# Wilssen_core_v0_206a.net
KiCad netlist of a schematic drawn in EAGLE
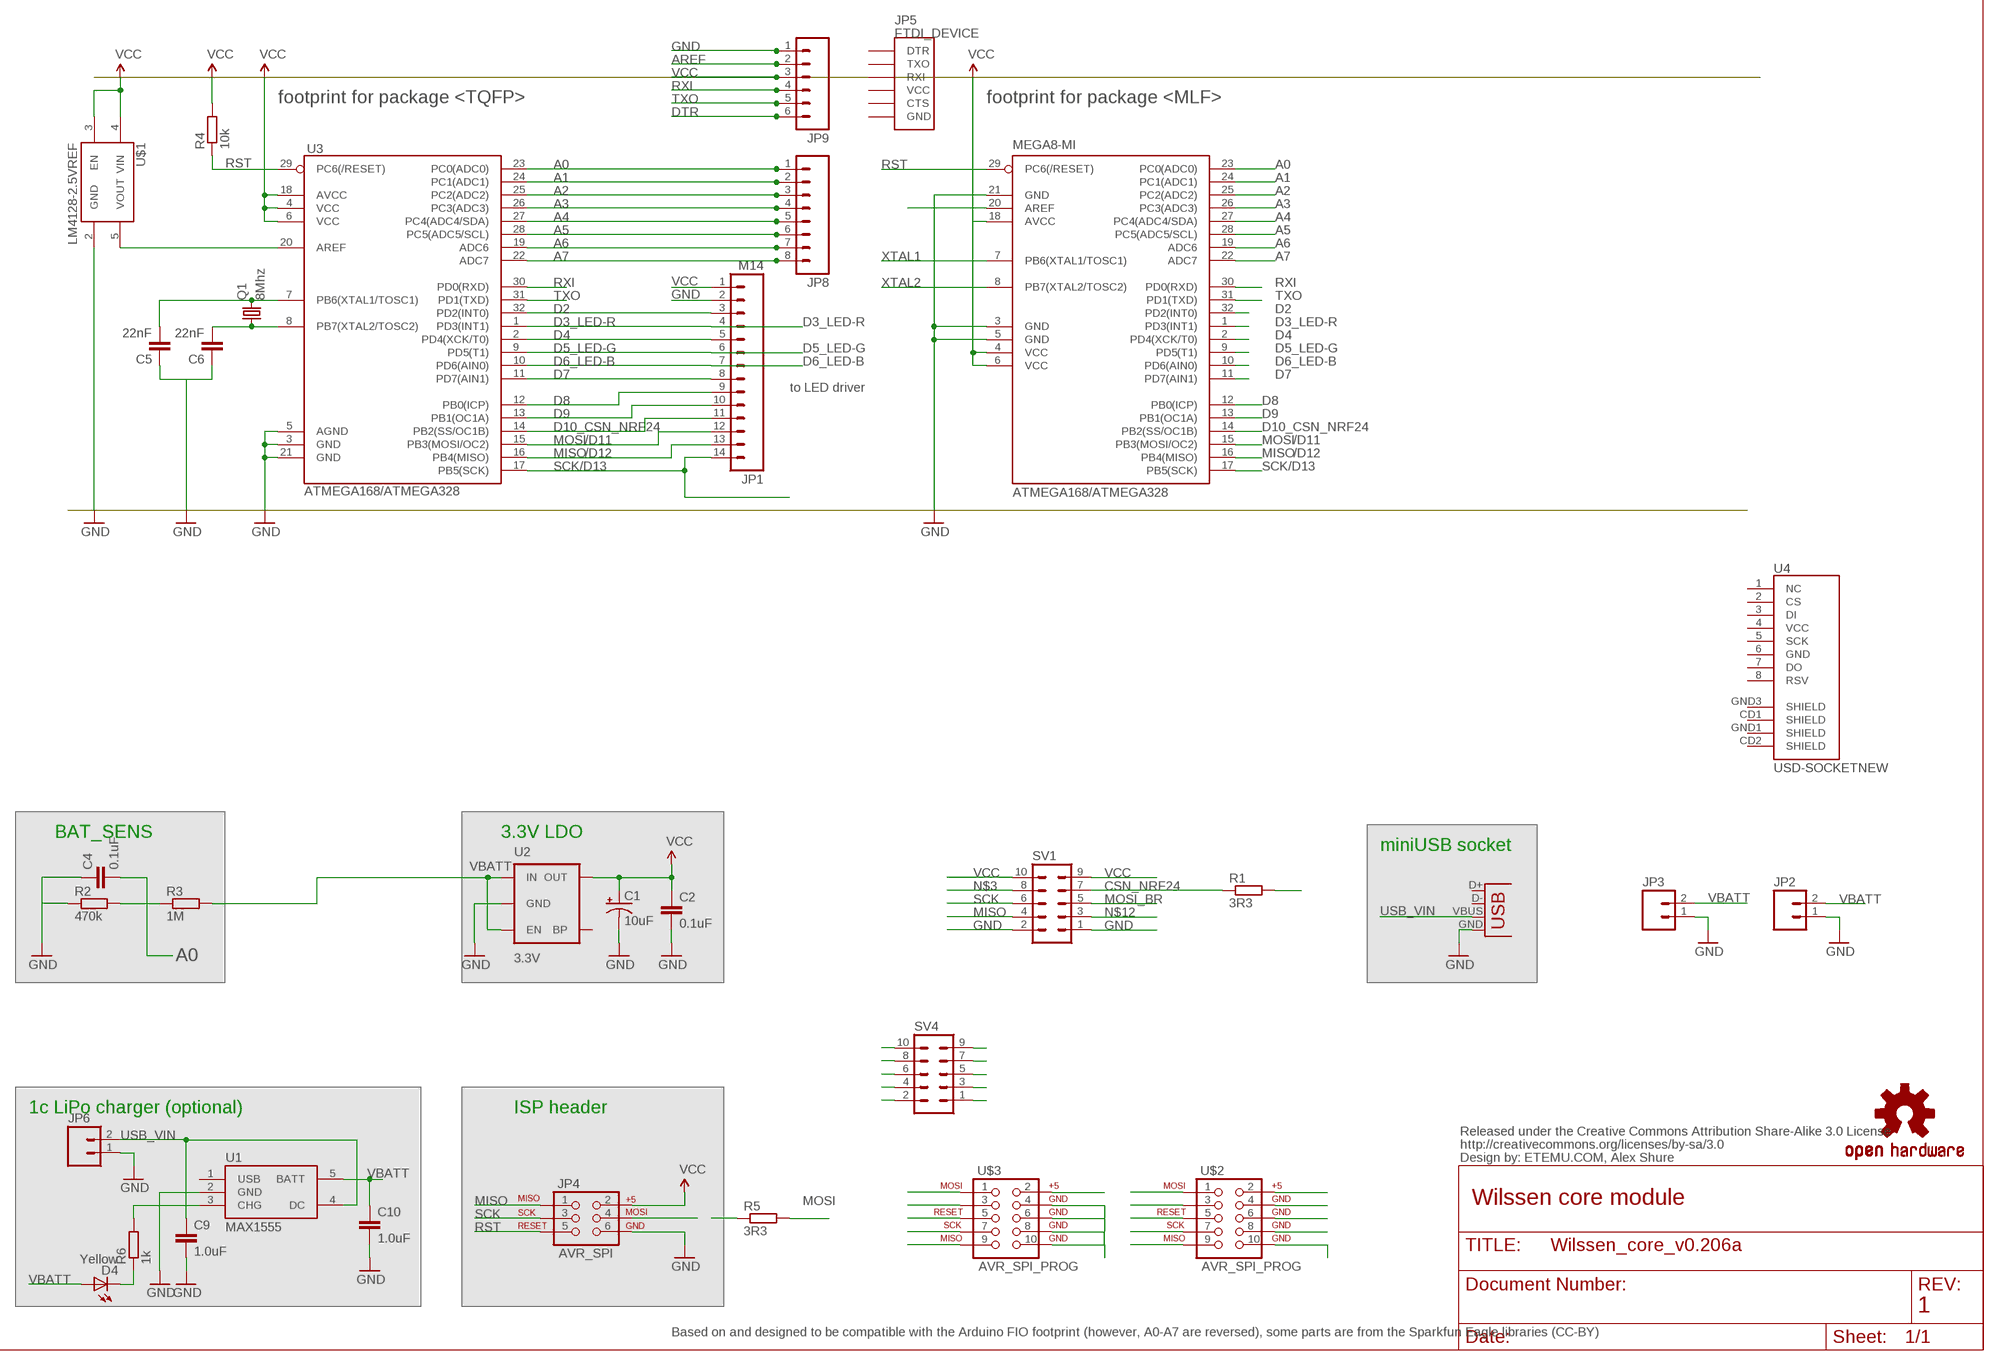
[diagram p0: schematic, sheet 1, part 1 of 2]
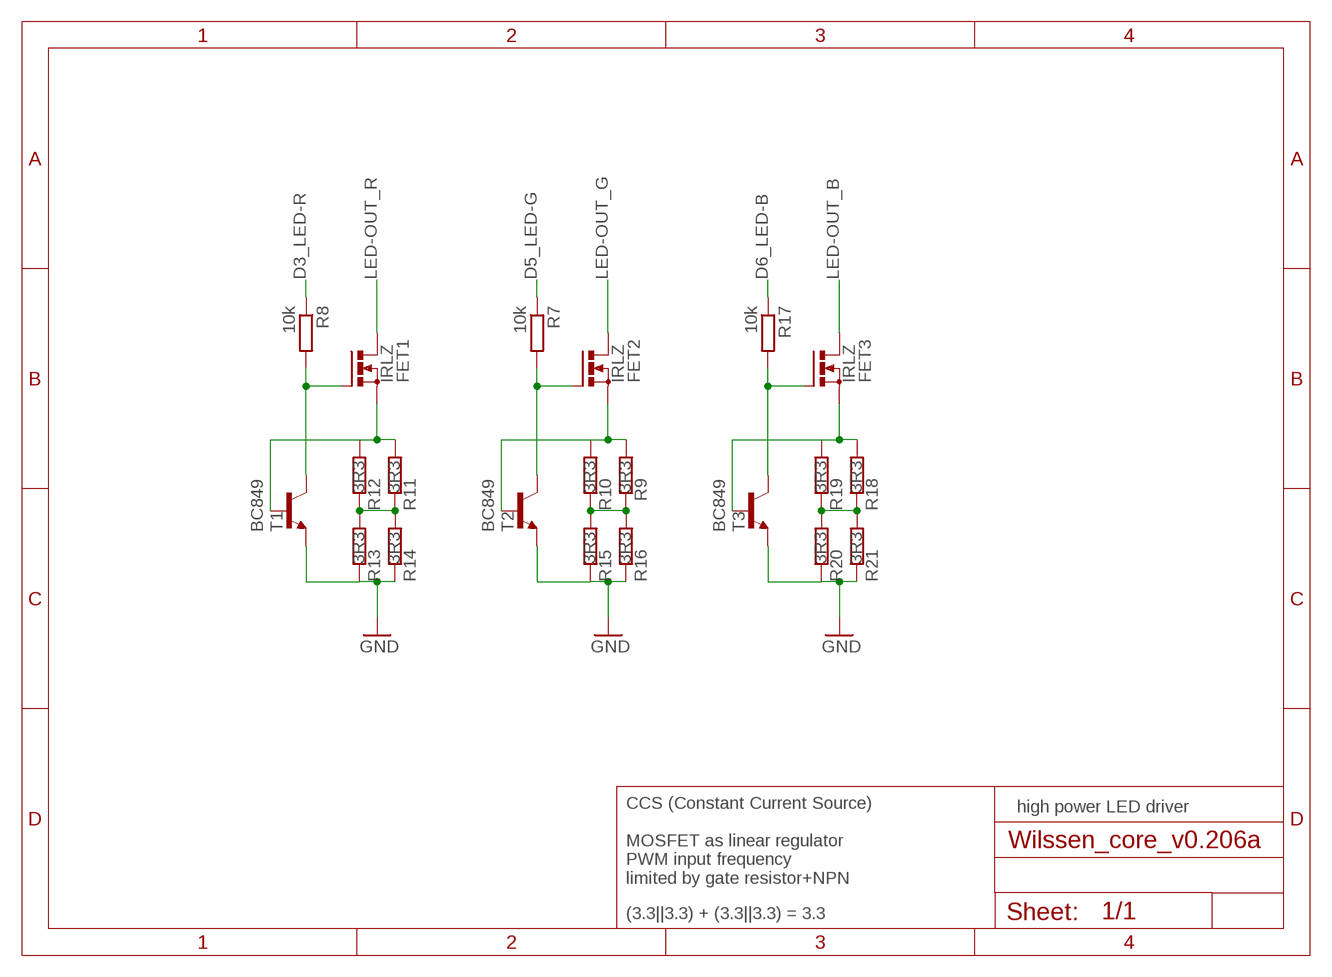
[diagram p1: schematic, sheet 1, part 2 of 2]

(export (version "E")
  (design (tool "Eeschema 10.0.6"))
  (components
    (comp (ref "ATMEGA168/ATMEGA328")
      (value "MEGA8-MI")
      (footprint "eagle-import:MLF32")
      (fields (field (name "MPN") "ATMEGA88PA-MU"))
      (libsource (lib "eagle-import") (part "MEGA8-MI"))
    )
    (comp (ref "C1")
      (value "10uF")
      (footprint "eagle-import:EIA3216")
      (libsource (lib "eagle-import") (part "CAP_POL1206"))
    )
    (comp (ref "C2")
      (value "0.1uF")
      (footprint "eagle-import:0805")
      (libsource (lib "eagle-import") (part "CAP0805"))
    )
    (comp (ref "C4")
      (value "0.1uF")
      (footprint "eagle-import:0805")
      (libsource (lib "eagle-import") (part "CAP0805"))
    )
    (comp (ref "C5")
      (value "22nF")
      (footprint "eagle-import:0805")
      (libsource (lib "eagle-import") (part "CAP0805"))
    )
    (comp (ref "C6")
      (value "22nF")
      (footprint "eagle-import:0805")
      (libsource (lib "eagle-import") (part "CAP0805"))
    )
    (comp (ref "C9")
      (value "1.0uF")
      (footprint "eagle-import:0805")
      (libsource (lib "eagle-import") (part "CAP0805"))
    )
    (comp (ref "C10")
      (value "1.0uF")
      (footprint "eagle-import:0805")
      (libsource (lib "eagle-import") (part "CAP0805"))
    )
    (comp (ref "CC_TEXT1")
      (value "CREATIVE_COMMONS")
      (footprint "eagle-import:CREATIVE_COMMONS")
      (libsource (lib "eagle-import") (part "CREATIVE_COMMONS"))
    )
    (comp (ref "D4")
      (value "Yellow")
      (footprint "eagle-import:LED-0603")
      (libsource (lib "eagle-import") (part "LED0603"))
    )
    (comp (ref "FET1")
      (value "IRLZ")
      (footprint "eagle-import:TO220BV")
      (libsource (lib "eagle-import") (part "PMOSFET_NTO220BV"))
    )
    (comp (ref "FET2")
      (value "IRLZ")
      (footprint "eagle-import:TO220BV")
      (libsource (lib "eagle-import") (part "PMOSFET_NTO220BV"))
    )
    (comp (ref "FET3")
      (value "IRLZ")
      (footprint "eagle-import:TO220BV")
      (libsource (lib "eagle-import") (part "PMOSFET_NTO220BV"))
    )
    (comp (ref "JP1")
      (value "M14")
      (footprint "eagle-import:1X14")
      (libsource (lib "eagle-import") (part "M14"))
    )
    (comp (ref "JP2")
      (value "M02PTH")
      (footprint "eagle-import:1X02")
      (libsource (lib "eagle-import") (part "M02PTH"))
    )
    (comp (ref "JP3")
      (value "M02-JST-2MM-SMT")
      (footprint "eagle-import:S2B-PH")
      (libsource (lib "eagle-import") (part "M02-JST-2MM-SMT"))
    )
    (comp (ref "JP4")
      (value "AVR_SPI")
      (footprint "eagle-import:2X3")
      (libsource (lib "eagle-import") (part "AVR_SPI_PRG_6PTH"))
    )
    (comp (ref "JP5")
      (value "FTDI_DEVICE")
      (footprint "eagle-import:FTDI_DEVICE_SIDE")
      (libsource (lib "eagle-import") (part "FTDI_DEVICE"))
    )
    (comp (ref "JP6")
      (value "M02PTH")
      (footprint "eagle-import:1X02")
      (libsource (lib "eagle-import") (part "M02PTH"))
    )
    (comp (ref "JP8")
      (value "M081X08")
      (footprint "eagle-import:1X08")
      (libsource (lib "eagle-import") (part "M081X08"))
    )
    (comp (ref "JP9")
      (value "M06SIP")
      (footprint "eagle-import:1X06")
      (libsource (lib "eagle-import") (part "M06SIP"))
    )
    (comp (ref "LOGO1")
      (value "OSHW-LOGOS")
      (footprint "eagle-import:OSHW-LOGO-S")
      (libsource (lib "eagle-import") (part "OSHW-LOGOS"))
    )
    (comp (ref "Q1")
      (value "8Mhz")
      (footprint "eagle-import:SM49")
      (libsource (lib "eagle-import") (part "CRYSTALSM49"))
    )
    (comp (ref "R1")
      (value "3R3")
      (footprint "eagle-import:R1206")
      (libsource (lib "eagle-import") (part "R-EU_R1206"))
    )
    (comp (ref "R2")
      (value "470k")
      (footprint "eagle-import:R0805")
      (libsource (lib "eagle-import") (part "R-EU_R0805"))
    )
    (comp (ref "R3")
      (value "1M")
      (footprint "eagle-import:R0805")
      (libsource (lib "eagle-import") (part "R-EU_R0805"))
    )
    (comp (ref "R4")
      (value "10k")
      (footprint "eagle-import:R0805")
      (libsource (lib "eagle-import") (part "R-EU_R0805"))
    )
    (comp (ref "R5")
      (value "3R3")
      (footprint "eagle-import:R1206")
      (libsource (lib "eagle-import") (part "R-EU_R1206"))
    )
    (comp (ref "R6")
      (value "1k")
      (footprint "eagle-import:R0805")
      (libsource (lib "eagle-import") (part "R-EU_R0805"))
    )
    (comp (ref "R7")
      (value "10k")
      (footprint "eagle-import:R0805")
      (libsource (lib "eagle-import") (part "resistor_R-EU_R0805"))
    )
    (comp (ref "R8")
      (value "10k")
      (footprint "eagle-import:R0805")
      (libsource (lib "eagle-import") (part "resistor_R-EU_R0805"))
    )
    (comp (ref "R9")
      (value "3R3")
      (footprint "eagle-import:R1206")
      (libsource (lib "eagle-import") (part "resistor_R-EU_R1206"))
    )
    (comp (ref "R10")
      (value "3R3")
      (footprint "eagle-import:R1206")
      (libsource (lib "eagle-import") (part "resistor_R-EU_R1206"))
    )
    (comp (ref "R11")
      (value "3R3")
      (footprint "eagle-import:R1206")
      (libsource (lib "eagle-import") (part "resistor_R-EU_R1206"))
    )
    (comp (ref "R12")
      (value "3R3")
      (footprint "eagle-import:R1206")
      (libsource (lib "eagle-import") (part "resistor_R-EU_R1206"))
    )
    (comp (ref "R13")
      (value "3R3")
      (footprint "eagle-import:R1206")
      (libsource (lib "eagle-import") (part "resistor_R-EU_R1206"))
    )
    (comp (ref "R14")
      (value "3R3")
      (footprint "eagle-import:R1206")
      (libsource (lib "eagle-import") (part "resistor_R-EU_R1206"))
    )
    (comp (ref "R15")
      (value "3R3")
      (footprint "eagle-import:R1206")
      (libsource (lib "eagle-import") (part "resistor_R-EU_R1206"))
    )
    (comp (ref "R16")
      (value "3R3")
      (footprint "eagle-import:R1206")
      (libsource (lib "eagle-import") (part "resistor_R-EU_R1206"))
    )
    (comp (ref "R17")
      (value "10k")
      (footprint "eagle-import:R0805")
      (libsource (lib "eagle-import") (part "resistor_R-EU_R0805"))
    )
    (comp (ref "R18")
      (value "3R3")
      (footprint "eagle-import:R1206")
      (libsource (lib "eagle-import") (part "resistor_R-EU_R1206"))
    )
    (comp (ref "R19")
      (value "3R3")
      (footprint "eagle-import:R1206")
      (libsource (lib "eagle-import") (part "resistor_R-EU_R1206"))
    )
    (comp (ref "R20")
      (value "3R3")
      (footprint "eagle-import:R1206")
      (libsource (lib "eagle-import") (part "resistor_R-EU_R1206"))
    )
    (comp (ref "R21")
      (value "3R3")
      (footprint "eagle-import:R1206")
      (libsource (lib "eagle-import") (part "resistor_R-EU_R1206"))
    )
    (comp (ref "SV1")
      (value "MA05-2")
      (footprint "eagle-import:MA05-2")
      (libsource (lib "eagle-import") (part "MA05-2"))
    )
    (comp (ref "SV4")
      (value "MA05-2")
      (footprint "eagle-import:MA05-2")
      (libsource (lib "eagle-import") (part "MA05-2"))
    )
    (comp (ref "T1")
      (value "BC849")
      (footprint "eagle-import:SOT23")
      (libsource (lib "eagle-import") (part "BC849"))
    )
    (comp (ref "T2")
      (value "BC849")
      (footprint "eagle-import:SOT23")
      (libsource (lib "eagle-import") (part "BC849"))
    )
    (comp (ref "T3")
      (value "BC849")
      (footprint "eagle-import:SOT23")
      (libsource (lib "eagle-import") (part "BC849"))
    )
    (comp (ref "U$1")
      (value "LM4128-2.5VREF")
      (footprint "eagle-import:SOT23-5")
      (libsource (lib "eagle-import") (part "LM4128-2.5VREF"))
    )
    (comp (ref "U$2")
      (value "AVR_SPI_PROG")
      (footprint "eagle-import:AVR_ICSP")
      (libsource (lib "eagle-import") (part "AVR_SPI_PROG"))
    )
    (comp (ref "U$3")
      (value "AVR_SPI_PROG")
      (footprint "eagle-import:AVR_ICSP")
      (libsource (lib "eagle-import") (part "AVR_SPI_PROG"))
    )
    (comp (ref "U1")
      (value "MAX1555")
      (footprint "eagle-import:SOT23-5")
      (libsource (lib "eagle-import") (part "MAX1555"))
    )
    (comp (ref "U2")
      (value "3.3V")
      (footprint "eagle-import:SOT23-5")
      (libsource (lib "eagle-import") (part "V_REG_LDOSMD"))
    )
    (comp (ref "U3")
      (value "ATMEGA168/ATMEGA328")
      (footprint "eagle-import:TQFP32-08")
      (libsource (lib "eagle-import") (part "ATMEGA168"))
    )
    (comp (ref "U4")
      (value "USD-SOCKETNEW")
      (footprint "eagle-import:MICRO-SD-SOCKET-PP")
      (libsource (lib "eagle-import") (part "USD-SOCKETNEW"))
    )
    (comp (ref "X1")
      (value "USBSMD")
      (footprint "eagle-import:USB-MINIB")
      (libsource (lib "eagle-import") (part "USBSMD"))
    )
  )
  (nets
    (net (code "1") (name "/A0") (class "Default")
      (node (ref "ATMEGA168/ATMEGA328") (pin "23") (pinfunction "PC0(ADC0)_23") (pintype "bidirectional"))
      (node (ref "C4") (pin "2") (pinfunction "2_2") (pintype "passive"))
      (node (ref "JP8") (pin "1") (pinfunction "1_1") (pintype "passive"))
      (node (ref "R2") (pin "2") (pinfunction "2_2") (pintype "passive"))
      (node (ref "R3") (pin "1") (pinfunction "1_1") (pintype "passive"))
      (node (ref "U3") (pin "23") (pinfunction "PC0(ADC0)_23") (pintype "bidirectional"))
    )
    (net (code "2") (name "/A1") (class "Default")
      (node (ref "ATMEGA168/ATMEGA328") (pin "24") (pinfunction "PC1(ADC1)_24") (pintype "bidirectional"))
      (node (ref "JP8") (pin "2") (pinfunction "2_2") (pintype "passive"))
      (node (ref "U3") (pin "24") (pinfunction "PC1(ADC1)_24") (pintype "bidirectional"))
    )
    (net (code "3") (name "/A2") (class "Default")
      (node (ref "ATMEGA168/ATMEGA328") (pin "25") (pinfunction "PC2(ADC2)_25") (pintype "bidirectional"))
      (node (ref "JP8") (pin "3") (pinfunction "3_3") (pintype "passive"))
      (node (ref "U3") (pin "25") (pinfunction "PC2(ADC2)_25") (pintype "bidirectional"))
    )
    (net (code "4") (name "/A3") (class "Default")
      (node (ref "ATMEGA168/ATMEGA328") (pin "26") (pinfunction "PC3(ADC3)_26") (pintype "bidirectional"))
      (node (ref "JP8") (pin "4") (pinfunction "4_4") (pintype "passive"))
      (node (ref "U3") (pin "26") (pinfunction "PC3(ADC3)_26") (pintype "bidirectional"))
    )
    (net (code "5") (name "/A4") (class "Default")
      (node (ref "ATMEGA168/ATMEGA328") (pin "27") (pinfunction "PC4(ADC4/SDA)_27") (pintype "bidirectional"))
      (node (ref "JP8") (pin "5") (pinfunction "5_5") (pintype "passive"))
      (node (ref "U3") (pin "27") (pinfunction "PC4(ADC4/SDA)_27") (pintype "bidirectional"))
    )
    (net (code "6") (name "/A5") (class "Default")
      (node (ref "ATMEGA168/ATMEGA328") (pin "28") (pinfunction "PC5(ADC5/SCL)_28") (pintype "bidirectional"))
      (node (ref "JP8") (pin "6") (pinfunction "6_6") (pintype "passive"))
      (node (ref "U3") (pin "28") (pinfunction "PC5(ADC5/SCL)_28") (pintype "bidirectional"))
    )
    (net (code "7") (name "/A6") (class "Default")
      (node (ref "ATMEGA168/ATMEGA328") (pin "19") (pinfunction "ADC6_19") (pintype "bidirectional"))
      (node (ref "JP8") (pin "7") (pinfunction "7_7") (pintype "passive"))
      (node (ref "U3") (pin "19") (pinfunction "ADC6_19") (pintype "bidirectional"))
    )
    (net (code "8") (name "/A7") (class "Default")
      (node (ref "ATMEGA168/ATMEGA328") (pin "22") (pinfunction "ADC7_22") (pintype "bidirectional"))
      (node (ref "JP8") (pin "8") (pinfunction "8_8") (pintype "passive"))
      (node (ref "U3") (pin "22") (pinfunction "ADC7_22") (pintype "bidirectional"))
    )
    (net (code "9") (name "/AREF") (class "Default")
      (node (ref "ATMEGA168/ATMEGA328") (pin "20") (pinfunction "AREF_20") (pintype "passive"))
      (node (ref "JP9") (pin "2") (pinfunction "2_2") (pintype "passive"))
      (node (ref "U$1") (pin "5") (pinfunction "VOUT_5") (pintype "bidirectional"))
      (node (ref "U3") (pin "20") (pinfunction "AREF_20") (pintype "bidirectional"))
    )
    (net (code "10") (name "/CSN") (class "Default")
      (node (ref "SV4") (pin "8") (pinfunction "8_8") (pintype "passive"))
      (node (ref "U$2") (pin "3") (pinfunction "3_3") (pintype "passive"))
    )
    (net (code "11") (name "/CSN_NRF24") (class "Default")
      (node (ref "R1") (pin "1") (pinfunction "1_1") (pintype "passive"))
      (node (ref "SV1") (pin "7") (pinfunction "7_7") (pintype "passive"))
    )
    (net (code "12") (name "/D2") (class "Default")
      (node (ref "ATMEGA168/ATMEGA328") (pin "32") (pinfunction "PD2(INT0)_32") (pintype "bidirectional"))
      (node (ref "JP1") (pin "3") (pinfunction "3_3") (pintype "passive"))
      (node (ref "U3") (pin "32") (pinfunction "PD2(INT0)_32") (pintype "bidirectional"))
    )
    (net (code "13") (name "/D3_LED-R") (class "Default")
      (node (ref "ATMEGA168/ATMEGA328") (pin "1") (pinfunction "PD3(INT1)_1") (pintype "bidirectional"))
      (node (ref "JP1") (pin "4") (pinfunction "4_4") (pintype "passive"))
      (node (ref "R8") (pin "1") (pinfunction "1_1") (pintype "passive"))
      (node (ref "U3") (pin "1") (pinfunction "PD3(INT1)_1") (pintype "bidirectional"))
    )
    (net (code "14") (name "/D4") (class "Default")
      (node (ref "ATMEGA168/ATMEGA328") (pin "2") (pinfunction "PD4(XCK/T0)_2") (pintype "bidirectional"))
      (node (ref "JP1") (pin "5") (pinfunction "5_5") (pintype "passive"))
      (node (ref "U3") (pin "2") (pinfunction "PD4(XCK/T0)_2") (pintype "bidirectional"))
    )
    (net (code "15") (name "/D5_LED-G") (class "Default")
      (node (ref "ATMEGA168/ATMEGA328") (pin "9") (pinfunction "PD5(T1)_9") (pintype "bidirectional"))
      (node (ref "JP1") (pin "6") (pinfunction "6_6") (pintype "passive"))
      (node (ref "R7") (pin "1") (pinfunction "1_1") (pintype "passive"))
      (node (ref "U3") (pin "9") (pinfunction "PD5(T1)_9") (pintype "bidirectional"))
    )
    (net (code "16") (name "/D6_LED-B") (class "Default")
      (node (ref "ATMEGA168/ATMEGA328") (pin "10") (pinfunction "PD6(AIN0)_10") (pintype "bidirectional"))
      (node (ref "JP1") (pin "7") (pinfunction "7_7") (pintype "passive"))
      (node (ref "R17") (pin "1") (pinfunction "1_1") (pintype "passive"))
      (node (ref "U3") (pin "10") (pinfunction "PD6(AIN0)_10") (pintype "bidirectional"))
    )
    (net (code "17") (name "/D7") (class "Default")
      (node (ref "ATMEGA168/ATMEGA328") (pin "11") (pinfunction "PD7(AIN1)_11") (pintype "bidirectional"))
      (node (ref "JP1") (pin "8") (pinfunction "8_8") (pintype "passive"))
      (node (ref "U3") (pin "11") (pinfunction "PD7(AIN1)_11") (pintype "bidirectional"))
    )
    (net (code "18") (name "/D8") (class "Default")
      (node (ref "ATMEGA168/ATMEGA328") (pin "12") (pinfunction "PB0(ICP)_12") (pintype "bidirectional"))
      (node (ref "JP1") (pin "9") (pinfunction "9_9") (pintype "passive"))
      (node (ref "U3") (pin "12") (pinfunction "PB0(ICP)_12") (pintype "bidirectional"))
    )
    (net (code "19") (name "/D9") (class "Default")
      (node (ref "ATMEGA168/ATMEGA328") (pin "13") (pinfunction "PB1(OC1A)_13") (pintype "bidirectional"))
      (node (ref "JP1") (pin "10") (pinfunction "10_10") (pintype "passive"))
      (node (ref "U3") (pin "13") (pinfunction "PB1(OC1A)_13") (pintype "bidirectional"))
    )
    (net (code "20") (name "/D10_CSN_NRF24") (class "Default")
      (node (ref "ATMEGA168/ATMEGA328") (pin "14") (pinfunction "PB2(SS/OC1B)_14") (pintype "bidirectional"))
      (node (ref "JP1") (pin "11") (pinfunction "11_11") (pintype "passive"))
      (node (ref "R1") (pin "2") (pinfunction "2_2") (pintype "passive"))
      (node (ref "U3") (pin "14") (pinfunction "PB2(SS/OC1B)_14") (pintype "bidirectional"))
    )
    (net (code "21") (name "/DTR") (class "Default")
      (node (ref "JP9") (pin "6") (pinfunction "6_6") (pintype "passive"))
    )
    (net (code "22") (name "/LED-OUT_B") (class "Default")
      (node (ref "FET3") (pin "D") (pinfunction "D_D") (pintype "passive"))
    )
    (net (code "23") (name "/LED-OUT_G") (class "Default")
      (node (ref "FET2") (pin "D") (pinfunction "D_D") (pintype "passive"))
    )
    (net (code "24") (name "/LED-OUT_R") (class "Default")
      (node (ref "FET1") (pin "D") (pinfunction "D_D") (pintype "passive"))
    )
    (net (code "25") (name "/MISO") (class "Default")
      (node (ref "ATMEGA168/ATMEGA328") (pin "16") (pinfunction "PB4(MISO)_16") (pintype "bidirectional"))
      (node (ref "JP1") (pin "13") (pinfunction "13_13") (pintype "passive"))
      (node (ref "JP4") (pin "1") (pinfunction "1_1") (pintype "passive"))
      (node (ref "SV1") (pin "4") (pinfunction "4_4") (pintype "passive"))
      (node (ref "SV4") (pin "2") (pinfunction "2_2") (pintype "passive"))
      (node (ref "U$2") (pin "9") (pinfunction "9_9") (pintype "passive"))
      (node (ref "U$3") (pin "9") (pinfunction "9_9") (pintype "passive"))
      (node (ref "U3") (pin "16") (pinfunction "PB4(MISO)_16") (pintype "bidirectional"))
    )
    (net (code "26") (name "/MOSI") (class "Default")
      (node (ref "ATMEGA168/ATMEGA328") (pin "15") (pinfunction "PB3(MOSI/OC2)_15") (pintype "bidirectional"))
      (node (ref "JP1") (pin "12") (pinfunction "12_12") (pintype "passive"))
      (node (ref "JP4") (pin "4") (pinfunction "4_4") (pintype "passive"))
      (node (ref "R5") (pin "2") (pinfunction "2_2") (pintype "passive"))
      (node (ref "SV4") (pin "10") (pinfunction "10_10") (pintype "passive"))
      (node (ref "U$2") (pin "1") (pinfunction "1_1") (pintype "passive"))
      (node (ref "U$3") (pin "1") (pinfunction "1_1") (pintype "passive"))
      (node (ref "U3") (pin "15") (pinfunction "PB3(MOSI/OC2)_15") (pintype "bidirectional"))
    )
    (net (code "27") (name "/MOSI_BR") (class "Default")
      (node (ref "SV1") (pin "5") (pinfunction "5_5") (pintype "passive"))
    )
    (net (code "28") (name "/N$3") (class "Default")
      (node (ref "SV1") (pin "8") (pinfunction "8_8") (pintype "passive"))
    )
    (net (code "29") (name "/N$12") (class "Default")
      (node (ref "SV1") (pin "3") (pinfunction "3_3") (pintype "passive"))
    )
    (net (code "30") (name "/RST") (class "Default")
      (node (ref "ATMEGA168/ATMEGA328") (pin "29") (pinfunction "PC6(/RESET)_29") (pintype "bidirectional"))
      (node (ref "JP4") (pin "5") (pinfunction "5_5") (pintype "passive"))
      (node (ref "R4") (pin "1") (pinfunction "1_1") (pintype "passive"))
      (node (ref "SV4") (pin "6") (pinfunction "6_6") (pintype "passive"))
      (node (ref "U$2") (pin "5") (pinfunction "5_5") (pintype "passive"))
      (node (ref "U$3") (pin "5") (pinfunction "5_5") (pintype "passive"))
      (node (ref "U3") (pin "29") (pinfunction "PC6(/RESET)_29") (pintype "bidirectional"))
    )
    (net (code "31") (name "/RXI") (class "Default")
      (node (ref "ATMEGA168/ATMEGA328") (pin "30") (pinfunction "PD0(RXD)_30") (pintype "bidirectional"))
      (node (ref "JP9") (pin "4") (pinfunction "4_4") (pintype "passive"))
      (node (ref "U3") (pin "30") (pinfunction "PD0(RXD)_30") (pintype "bidirectional"))
    )
    (net (code "32") (name "/SCK") (class "Default")
      (node (ref "ATMEGA168/ATMEGA328") (pin "17") (pinfunction "PB5(SCK)_17") (pintype "bidirectional"))
      (node (ref "JP1") (pin "14") (pinfunction "14_14") (pintype "passive"))
      (node (ref "JP4") (pin "3") (pinfunction "3_3") (pintype "passive"))
      (node (ref "SV1") (pin "6") (pinfunction "6_6") (pintype "passive"))
      (node (ref "SV4") (pin "4") (pinfunction "4_4") (pintype "passive"))
      (node (ref "U$2") (pin "7") (pinfunction "7_7") (pintype "passive"))
      (node (ref "U$3") (pin "7") (pinfunction "7_7") (pintype "passive"))
      (node (ref "U3") (pin "17") (pinfunction "PB5(SCK)_17") (pintype "bidirectional"))
    )
    (net (code "33") (name "/TXO") (class "Default")
      (node (ref "ATMEGA168/ATMEGA328") (pin "31") (pinfunction "PD1(TXD)_31") (pintype "bidirectional"))
      (node (ref "JP9") (pin "5") (pinfunction "5_5") (pintype "passive"))
      (node (ref "U3") (pin "31") (pinfunction "PD1(TXD)_31") (pintype "bidirectional"))
    )
    (net (code "34") (name "/USB_VIN") (class "Default")
      (node (ref "C9") (pin "1") (pinfunction "1_1") (pintype "passive"))
      (node (ref "JP6") (pin "2") (pinfunction "2_2") (pintype "passive"))
      (node (ref "U1") (pin "4") (pinfunction "DC_4") (pintype "bidirectional"))
      (node (ref "X1") (pin "VBUS") (pinfunction "VBUS_VBUS") (pintype "bidirectional"))
    )
    (net (code "35") (name "/VBATT") (class "Default")
      (node (ref "C10") (pin "1") (pinfunction "1_1") (pintype "passive"))
      (node (ref "D4") (pin "A") (pinfunction "A_A") (pintype "passive"))
      (node (ref "JP2") (pin "2") (pinfunction "2_2") (pintype "passive"))
      (node (ref "JP3") (pin "2") (pinfunction "2_2") (pintype "passive"))
      (node (ref "R3") (pin "2") (pinfunction "2_2") (pintype "passive"))
      (node (ref "U1") (pin "5") (pinfunction "BATT_5") (pintype "bidirectional"))
      (node (ref "U2") (pin "1") (pinfunction "IN_1") (pintype "input"))
      (node (ref "U2") (pin "3") (pinfunction "EN_3") (pintype "input"))
    )
    (net (code "36") (name "/XTAL1") (class "Default")
      (node (ref "ATMEGA168/ATMEGA328") (pin "7") (pinfunction "PB6(XTAL1/TOSC1)_7") (pintype "bidirectional"))
      (node (ref "C5") (pin "2") (pinfunction "2_2") (pintype "passive"))
      (node (ref "Q1") (pin "2") (pinfunction "2_2") (pintype "passive"))
      (node (ref "U3") (pin "7") (pinfunction "PB6(XTAL1/TOSC1)_7") (pintype "bidirectional"))
    )
    (net (code "37") (name "/XTAL2") (class "Default")
      (node (ref "ATMEGA168/ATMEGA328") (pin "8") (pinfunction "PB7(XTAL2/TOSC2)_8") (pintype "bidirectional"))
      (node (ref "C6") (pin "2") (pinfunction "2_2") (pintype "passive"))
      (node (ref "Q1") (pin "1") (pinfunction "1_1") (pintype "passive"))
      (node (ref "U3") (pin "8") (pinfunction "PB7(XTAL2/TOSC2)_8") (pintype "bidirectional"))
    )
    (net (code "38") (name "GND") (class "Default")
      (node (ref "ATMEGA168/ATMEGA328") (pin "21") (pinfunction "GND_21") (pintype "power_in"))
      (node (ref "ATMEGA168/ATMEGA328") (pin "3") (pinfunction "GND_3") (pintype "power_in"))
      (node (ref "ATMEGA168/ATMEGA328") (pin "5") (pinfunction "GND_5") (pintype "power_in"))
      (node (ref "C1") (pin "C") (pinfunction "-_C") (pintype "passive"))
      (node (ref "C10") (pin "2") (pinfunction "2_2") (pintype "passive"))
      (node (ref "C2") (pin "2") (pinfunction "2_2") (pintype "passive"))
      (node (ref "C4") (pin "1") (pinfunction "1_1") (pintype "passive"))
      (node (ref "C5") (pin "1") (pinfunction "1_1") (pintype "passive"))
      (node (ref "C6") (pin "1") (pinfunction "1_1") (pintype "passive"))
      (node (ref "C9") (pin "2") (pinfunction "2_2") (pintype "passive"))
      (node (ref "JP1") (pin "2") (pinfunction "2_2") (pintype "passive"))
      (node (ref "JP2") (pin "1") (pinfunction "1_1") (pintype "passive"))
      (node (ref "JP3") (pin "1") (pinfunction "1_1") (pintype "passive"))
      (node (ref "JP4") (pin "6") (pinfunction "6_6") (pintype "passive"))
      (node (ref "JP6") (pin "1") (pinfunction "1_1") (pintype "passive"))
      (node (ref "JP9") (pin "1") (pinfunction "1_1") (pintype "passive"))
      (node (ref "R13") (pin "2") (pinfunction "2_2") (pintype "passive"))
      (node (ref "R14") (pin "2") (pinfunction "2_2") (pintype "passive"))
      (node (ref "R15") (pin "2") (pinfunction "2_2") (pintype "passive"))
      (node (ref "R16") (pin "2") (pinfunction "2_2") (pintype "passive"))
      (node (ref "R2") (pin "1") (pinfunction "1_1") (pintype "passive"))
      (node (ref "R20") (pin "2") (pinfunction "2_2") (pintype "passive"))
      (node (ref "R21") (pin "2") (pinfunction "2_2") (pintype "passive"))
      (node (ref "SV1") (pin "1") (pinfunction "1_1") (pintype "passive"))
      (node (ref "SV1") (pin "2") (pinfunction "2_2") (pintype "passive"))
      (node (ref "SV4") (pin "1") (pinfunction "1_1") (pintype "passive"))
      (node (ref "SV4") (pin "3") (pinfunction "3_3") (pintype "passive"))
      (node (ref "SV4") (pin "5") (pinfunction "5_5") (pintype "passive"))
      (node (ref "SV4") (pin "7") (pinfunction "7_7") (pintype "passive"))
      (node (ref "T1") (pin "2") (pinfunction "E_2") (pintype "passive"))
      (node (ref "T2") (pin "2") (pinfunction "E_2") (pintype "passive"))
      (node (ref "T3") (pin "2") (pinfunction "E_2") (pintype "passive"))
      (node (ref "U$1") (pin "2") (pinfunction "GND_2") (pintype "bidirectional"))
      (node (ref "U$2") (pin "10") (pinfunction "10_10") (pintype "passive"))
      (node (ref "U$3") (pin "10") (pinfunction "10_10") (pintype "passive"))
      (node (ref "U$3") (pin "4") (pinfunction "4_4") (pintype "passive"))
      (node (ref "U$3") (pin "6") (pinfunction "6_6") (pintype "passive"))
      (node (ref "U$3") (pin "8") (pinfunction "8_8") (pintype "passive"))
      (node (ref "U1") (pin "2") (pinfunction "GND_2") (pintype "bidirectional"))
      (node (ref "U2") (pin "2") (pinfunction "GND_2") (pintype "input"))
      (node (ref "U3") (pin "21") (pinfunction "GND_21") (pintype "bidirectional"))
      (node (ref "U3") (pin "3") (pinfunction "GND_3") (pintype "bidirectional"))
      (node (ref "U3") (pin "5") (pinfunction "AGND_5") (pintype "bidirectional"))
      (node (ref "X1") (pin "GND") (pinfunction "GND_GND") (pintype "bidirectional"))
    )
    (net (code "39") (name "Net-(D4-PadC)") (class "Default")
      (node (ref "D4") (pin "C") (pinfunction "C_C") (pintype "passive"))
      (node (ref "R6") (pin "1") (pinfunction "1_1") (pintype "passive"))
    )
    (net (code "40") (name "Net-(R10-Pad2)") (class "Default")
      (node (ref "R10") (pin "2") (pinfunction "2_2") (pintype "passive"))
      (node (ref "R15") (pin "1") (pinfunction "1_1") (pintype "passive"))
      (node (ref "R16") (pin "1") (pinfunction "1_1") (pintype "passive"))
      (node (ref "R9") (pin "2") (pinfunction "2_2") (pintype "passive"))
    )
    (net (code "41") (name "Net-(R11-Pad2)") (class "Default")
      (node (ref "R11") (pin "2") (pinfunction "2_2") (pintype "passive"))
      (node (ref "R12") (pin "2") (pinfunction "2_2") (pintype "passive"))
      (node (ref "R13") (pin "1") (pinfunction "1_1") (pintype "passive"))
      (node (ref "R14") (pin "1") (pinfunction "1_1") (pintype "passive"))
    )
    (net (code "42") (name "Net-(R18-Pad2)") (class "Default")
      (node (ref "R18") (pin "2") (pinfunction "2_2") (pintype "passive"))
      (node (ref "R19") (pin "2") (pinfunction "2_2") (pintype "passive"))
      (node (ref "R20") (pin "1") (pinfunction "1_1") (pintype "passive"))
      (node (ref "R21") (pin "1") (pinfunction "1_1") (pintype "passive"))
    )
    (net (code "43") (name "Net-(T1-B)") (class "Default")
      (node (ref "FET1") (pin "S") (pinfunction "S_S") (pintype "passive"))
      (node (ref "R11") (pin "1") (pinfunction "1_1") (pintype "passive"))
      (node (ref "R12") (pin "1") (pinfunction "1_1") (pintype "passive"))
      (node (ref "T1") (pin "1") (pinfunction "B_1") (pintype "passive"))
    )
    (net (code "44") (name "Net-(T1-C)") (class "Default")
      (node (ref "FET1") (pin "G") (pinfunction "G_G") (pintype "passive"))
      (node (ref "R8") (pin "2") (pinfunction "2_2") (pintype "passive"))
      (node (ref "T1") (pin "3") (pinfunction "C_3") (pintype "passive"))
    )
    (net (code "45") (name "Net-(T2-B)") (class "Default")
      (node (ref "FET2") (pin "S") (pinfunction "S_S") (pintype "passive"))
      (node (ref "R10") (pin "1") (pinfunction "1_1") (pintype "passive"))
      (node (ref "R9") (pin "1") (pinfunction "1_1") (pintype "passive"))
      (node (ref "T2") (pin "1") (pinfunction "B_1") (pintype "passive"))
    )
    (net (code "46") (name "Net-(T2-C)") (class "Default")
      (node (ref "FET2") (pin "G") (pinfunction "G_G") (pintype "passive"))
      (node (ref "R7") (pin "2") (pinfunction "2_2") (pintype "passive"))
      (node (ref "T2") (pin "3") (pinfunction "C_3") (pintype "passive"))
    )
    (net (code "47") (name "Net-(T3-B)") (class "Default")
      (node (ref "FET3") (pin "S") (pinfunction "S_S") (pintype "passive"))
      (node (ref "R18") (pin "1") (pinfunction "1_1") (pintype "passive"))
      (node (ref "R19") (pin "1") (pinfunction "1_1") (pintype "passive"))
      (node (ref "T3") (pin "1") (pinfunction "B_1") (pintype "passive"))
    )
    (net (code "48") (name "Net-(T3-C)") (class "Default")
      (node (ref "FET3") (pin "G") (pinfunction "G_G") (pintype "passive"))
      (node (ref "R17") (pin "2") (pinfunction "2_2") (pintype "passive"))
      (node (ref "T3") (pin "3") (pinfunction "C_3") (pintype "passive"))
    )
    (net (code "49") (name "Net-(U1-CHG)") (class "Default")
      (node (ref "R6") (pin "2") (pinfunction "2_2") (pintype "passive"))
      (node (ref "U1") (pin "3") (pinfunction "CHG_3") (pintype "bidirectional"))
    )
    (net (code "50") (name "VCC") (class "Default")
      (node (ref "ATMEGA168/ATMEGA328") (pin "18") (pinfunction "AVCC_18") (pintype "power_in"))
      (node (ref "ATMEGA168/ATMEGA328") (pin "4") (pinfunction "VCC_4") (pintype "power_in"))
      (node (ref "ATMEGA168/ATMEGA328") (pin "6") (pinfunction "VCC_6") (pintype "power_in"))
      (node (ref "C1") (pin "A") (pinfunction "+_A") (pintype "passive"))
      (node (ref "C2") (pin "1") (pinfunction "1_1") (pintype "passive"))
      (node (ref "JP1") (pin "1") (pinfunction "1_1") (pintype "passive"))
      (node (ref "JP4") (pin "2") (pinfunction "2_2") (pintype "passive"))
      (node (ref "JP9") (pin "3") (pinfunction "3_3") (pintype "passive"))
      (node (ref "R4") (pin "2") (pinfunction "2_2") (pintype "passive"))
      (node (ref "SV1") (pin "10") (pinfunction "10_10") (pintype "passive"))
      (node (ref "SV1") (pin "9") (pinfunction "9_9") (pintype "passive"))
      (node (ref "SV4") (pin "9") (pinfunction "9_9") (pintype "passive"))
      (node (ref "U$1") (pin "3") (pinfunction "EN_3") (pintype "bidirectional"))
      (node (ref "U$1") (pin "4") (pinfunction "VIN_4") (pintype "bidirectional"))
      (node (ref "U$2") (pin "2") (pinfunction "2_2") (pintype "passive"))
      (node (ref "U$3") (pin "2") (pinfunction "2_2") (pintype "passive"))
      (node (ref "U2") (pin "5") (pinfunction "OUT_5") (pintype "passive"))
      (node (ref "U3") (pin "18") (pinfunction "AVCC_18") (pintype "bidirectional"))
      (node (ref "U3") (pin "4") (pinfunction "VCC_4") (pintype "bidirectional"))
      (node (ref "U3") (pin "6") (pinfunction "VCC_6") (pintype "bidirectional"))
    )
    (net (code "51") (name "unconnected-(JP5-CTS-PadP$5)") (class "Default")
      (node (ref "JP5") (pin "P$5") (pinfunction "CTS_P$5") (pintype "bidirectional"))
    )
    (net (code "52") (name "unconnected-(JP5-DTR-PadP$1)") (class "Default")
      (node (ref "JP5") (pin "P$1") (pinfunction "DTR_P$1") (pintype "bidirectional"))
    )
    (net (code "53") (name "unconnected-(JP5-GND-PadP$6)") (class "Default")
      (node (ref "JP5") (pin "P$6") (pinfunction "GND_P$6") (pintype "bidirectional"))
    )
    (net (code "54") (name "unconnected-(JP5-RXI-PadP$3)") (class "Default")
      (node (ref "JP5") (pin "P$3") (pinfunction "RXI_P$3") (pintype "bidirectional"))
    )
    (net (code "55") (name "unconnected-(JP5-TXO-PadP$2)") (class "Default")
      (node (ref "JP5") (pin "P$2") (pinfunction "TXO_P$2") (pintype "bidirectional"))
    )
    (net (code "56") (name "unconnected-(JP5-VCC-PadP$4)") (class "Default")
      (node (ref "JP5") (pin "P$4") (pinfunction "VCC_P$4") (pintype "bidirectional"))
    )
    (net (code "57") (name "unconnected-(R5-Pad1)") (class "Default")
      (node (ref "R5") (pin "1") (pinfunction "1_1") (pintype "passive"))
    )
    (net (code "58") (name "unconnected-(U$2-Pad4)") (class "Default")
      (node (ref "U$2") (pin "4") (pinfunction "4_4") (pintype "passive"))
    )
    (net (code "59") (name "unconnected-(U$2-Pad6)") (class "Default")
      (node (ref "U$2") (pin "6") (pinfunction "6_6") (pintype "passive"))
    )
    (net (code "60") (name "unconnected-(U$2-Pad8)") (class "Default")
      (node (ref "U$2") (pin "8") (pinfunction "8_8") (pintype "passive"))
    )
    (net (code "61") (name "unconnected-(U$3-Pad3)") (class "Default")
      (node (ref "U$3") (pin "3") (pinfunction "3_3") (pintype "passive"))
    )
    (net (code "62") (name "unconnected-(U1-USB-Pad1)") (class "Default")
      (node (ref "U1") (pin "1") (pinfunction "USB_1") (pintype "bidirectional"))
    )
    (net (code "63") (name "unconnected-(U2-BP-Pad4)") (class "Default")
      (node (ref "U2") (pin "4") (pinfunction "BP_4") (pintype "input"))
    )
    (net (code "64") (name "unconnected-(U4-CS-Pad2)") (class "Default")
      (node (ref "U4") (pin "2") (pinfunction "CS_2") (pintype "bidirectional"))
    )
    (net (code "65") (name "unconnected-(U4-DI-Pad3)") (class "Default")
      (node (ref "U4") (pin "3") (pinfunction "DI_3") (pintype "bidirectional"))
    )
    (net (code "66") (name "unconnected-(U4-DO-Pad7)") (class "Default")
      (node (ref "U4") (pin "7") (pinfunction "DO_7") (pintype "bidirectional"))
    )
    (net (code "67") (name "unconnected-(U4-GND-Pad6)") (class "Default")
      (node (ref "U4") (pin "6") (pinfunction "GND_6") (pintype "bidirectional"))
    )
    (net (code "68") (name "unconnected-(U4-NC-Pad1)") (class "Default")
      (node (ref "U4") (pin "1") (pinfunction "NC_1") (pintype "bidirectional"))
    )
    (net (code "69") (name "unconnected-(U4-RSV-Pad8)") (class "Default")
      (node (ref "U4") (pin "8") (pinfunction "RSV_8") (pintype "bidirectional"))
    )
    (net (code "70") (name "unconnected-(U4-SCK-Pad5)") (class "Default")
      (node (ref "U4") (pin "5") (pinfunction "SCK_5") (pintype "bidirectional"))
    )
    (net (code "71") (name "unconnected-(U4-SHIELD-PadCD1)") (class "Default")
      (node (ref "U4") (pin "CD1") (pinfunction "SHIELD_CD1") (pintype "bidirectional"))
    )
    (net (code "72") (name "unconnected-(U4-SHIELD-PadCD2)") (class "Default")
      (node (ref "U4") (pin "CD2") (pinfunction "SHIELD_CD2") (pintype "bidirectional"))
    )
    (net (code "73") (name "unconnected-(U4-SHIELD-PadGND1)") (class "Default")
      (node (ref "U4") (pin "GND1") (pinfunction "SHIELD_GND1") (pintype "bidirectional"))
    )
    (net (code "74") (name "unconnected-(U4-SHIELD-PadGND3)") (class "Default")
      (node (ref "U4") (pin "GND3") (pinfunction "SHIELD_GND3") (pintype "bidirectional"))
    )
    (net (code "75") (name "unconnected-(U4-VCC-Pad4)") (class "Default")
      (node (ref "U4") (pin "4") (pinfunction "VCC_4") (pintype "bidirectional"))
    )
    (net (code "76") (name "unconnected-(X1-PadD+)") (class "Default")
      (node (ref "X1") (pin "D+") (pinfunction "D+_D+") (pintype "bidirectional"))
    )
    (net (code "77") (name "unconnected-(X1-PadD-)") (class "Default")
      (node (ref "X1") (pin "D-") (pinfunction "D-_D-") (pintype "bidirectional"))
    )
  )
)
